# Motor.net
KiCad netlist of a schematic drawn in EAGLE
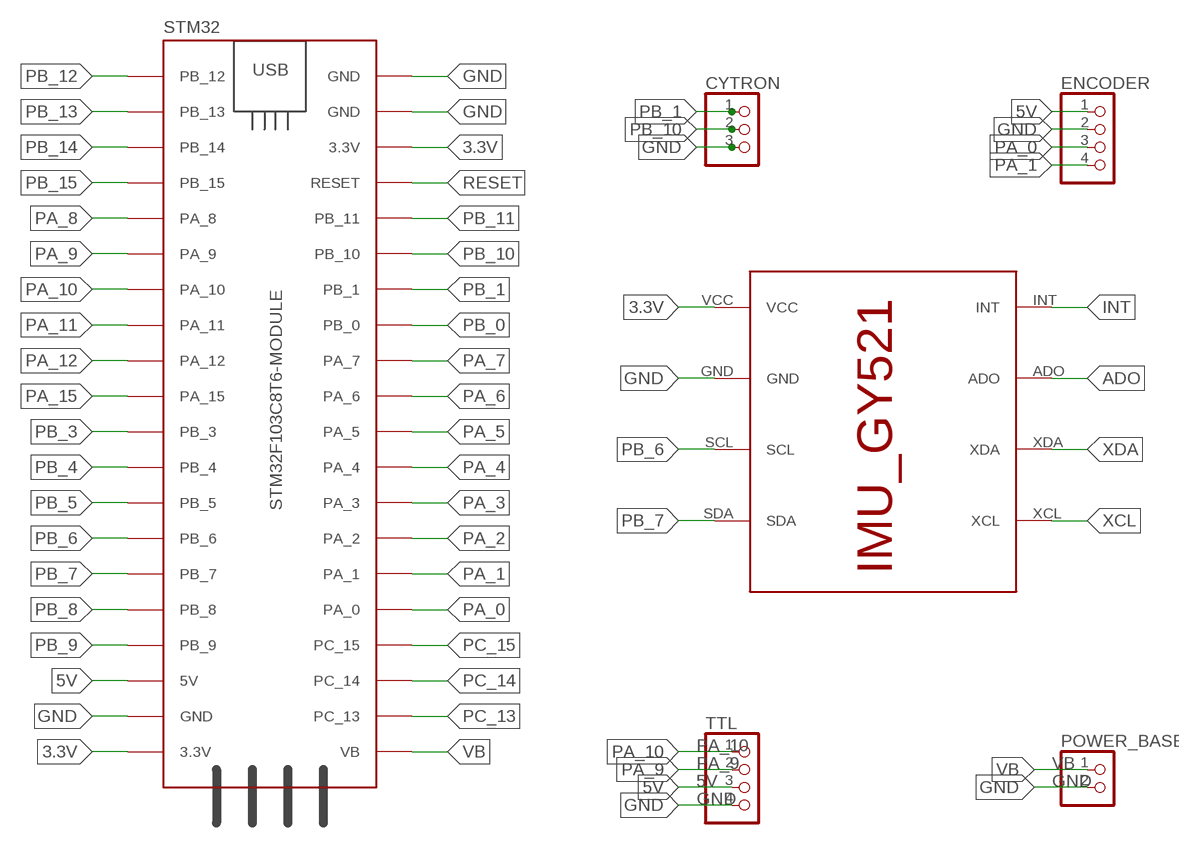
[diagram p0: schematic, sheet 1]

(export (version "E")
  (design (tool "Eeschema 10.0.6"))
  (components
    (comp (ref "CYTRON")
      (value "PINHD-3_DATA")
      (footprint "eagle-import:1X03_DATA")
      (libsource (lib "eagle-import") (part "PINHD-3_DATA"))
    )
    (comp (ref "ENCODER")
      (value "PINHD-4_DATA")
      (footprint "eagle-import:1X04_DATA")
      (libsource (lib "eagle-import") (part "PINHD-4_DATA"))
    )
    (comp (ref "IMU")
      (value "IMU_ROBOCON_GY521")
      (footprint "eagle-import:IMU_GY521")
      (libsource (lib "eagle-import") (part "IMU_ROBOCON_GY521"))
    )
    (comp (ref "POWER_BASE")
      (value "PINHD-2_DATA")
      (footprint "eagle-import:1X02_DATA")
      (libsource (lib "eagle-import") (part "PINHD-2_DATA"))
    )
    (comp (ref "STM32")
      (value "STM32F103C8T6-MODULE")
      (footprint "eagle-import:STM32F103C8T6-MODULE")
      (libsource (lib "eagle-import") (part "STM32F103C8T6-MODULE"))
    )
    (comp (ref "TTL")
      (value "PINHD-4_DATA")
      (footprint "eagle-import:1X04_DATA")
      (libsource (lib "eagle-import") (part "PINHD-4_DATA"))
    )
  )
  (nets
    (net (code "1") (name "3.3V") (class "Default")
      (node (ref "IMU") (pin "VCC") (pinfunction "VCC_VCC") (pintype "bidirectional"))
      (node (ref "STM32") (pin "3.3V_1") (pinfunction "3.3V_3.3V_1") (pintype "bidirectional"))
      (node (ref "STM32") (pin "3.3V_2") (pinfunction "3.3V_3.3V_2") (pintype "bidirectional"))
    )
    (net (code "2") (name "5V") (class "Default")
      (node (ref "ENCODER") (pin "1") (pinfunction "1_1") (pintype "passive"))
      (node (ref "STM32") (pin "5V") (pinfunction "5V_5V") (pintype "bidirectional"))
      (node (ref "TTL") (pin "3") (pinfunction "3_3") (pintype "passive"))
    )
    (net (code "3") (name "ADO") (class "Default")
      (node (ref "IMU") (pin "ADO") (pinfunction "ADO_ADO") (pintype "bidirectional"))
    )
    (net (code "4") (name "GND") (class "Default")
      (node (ref "CYTRON") (pin "3") (pinfunction "3_3") (pintype "passive"))
      (node (ref "ENCODER") (pin "2") (pinfunction "2_2") (pintype "passive"))
      (node (ref "IMU") (pin "GND") (pinfunction "GND_GND") (pintype "bidirectional"))
      (node (ref "POWER_BASE") (pin "2") (pinfunction "2_2") (pintype "passive"))
      (node (ref "STM32") (pin "GND_1") (pinfunction "GND_GND_1") (pintype "bidirectional"))
      (node (ref "STM32") (pin "GND_2") (pinfunction "GND_GND_2") (pintype "bidirectional"))
      (node (ref "STM32") (pin "GND_3") (pinfunction "GND_GND_3") (pintype "power_in"))
      (node (ref "TTL") (pin "4") (pinfunction "4_4") (pintype "passive"))
    )
    (net (code "5") (name "INT") (class "Default")
      (node (ref "IMU") (pin "INT") (pinfunction "INT_INT") (pintype "bidirectional"))
    )
    (net (code "6") (name "PA_0") (class "Default")
      (node (ref "ENCODER") (pin "3") (pinfunction "3_3") (pintype "passive"))
      (node (ref "STM32") (pin "PA_0") (pinfunction "PA_0_PA_0") (pintype "bidirectional"))
    )
    (net (code "7") (name "PA_1") (class "Default")
      (node (ref "ENCODER") (pin "4") (pinfunction "4_4") (pintype "passive"))
      (node (ref "STM32") (pin "PA_1") (pinfunction "PA_1_PA_1") (pintype "bidirectional"))
    )
    (net (code "8") (name "PA_2") (class "Default")
      (node (ref "STM32") (pin "PA_2") (pinfunction "PA_2_PA_2") (pintype "bidirectional"))
    )
    (net (code "9") (name "PA_3") (class "Default")
      (node (ref "STM32") (pin "PA_3") (pinfunction "PA_3_PA_3") (pintype "bidirectional"))
    )
    (net (code "10") (name "PA_4") (class "Default")
      (node (ref "STM32") (pin "PA_4") (pinfunction "PA_4_PA_4") (pintype "bidirectional"))
    )
    (net (code "11") (name "PA_5") (class "Default")
      (node (ref "STM32") (pin "PA_5") (pinfunction "PA_5_PA_5") (pintype "bidirectional"))
    )
    (net (code "12") (name "PA_6") (class "Default")
      (node (ref "STM32") (pin "PA_6") (pinfunction "PA_6_PA_6") (pintype "bidirectional"))
    )
    (net (code "13") (name "PA_7") (class "Default")
      (node (ref "STM32") (pin "PA_7") (pinfunction "PA_7_PA_7") (pintype "bidirectional"))
    )
    (net (code "14") (name "PA_8") (class "Default")
      (node (ref "STM32") (pin "PA_8") (pinfunction "PA_8_PA_8") (pintype "bidirectional"))
    )
    (net (code "15") (name "PA_9") (class "Default")
      (node (ref "STM32") (pin "PA_9") (pinfunction "PA_9_PA_9") (pintype "bidirectional"))
      (node (ref "TTL") (pin "2") (pinfunction "2_2") (pintype "passive"))
    )
    (net (code "16") (name "PA_10") (class "Default")
      (node (ref "STM32") (pin "PA_10") (pinfunction "PA_10_PA_10") (pintype "bidirectional"))
      (node (ref "TTL") (pin "1") (pinfunction "1_1") (pintype "passive"))
    )
    (net (code "17") (name "PA_11") (class "Default")
      (node (ref "STM32") (pin "PA_11") (pinfunction "PA_11_PA_11") (pintype "bidirectional"))
    )
    (net (code "18") (name "PA_12") (class "Default")
      (node (ref "STM32") (pin "PA_12") (pinfunction "PA_12_PA_12") (pintype "bidirectional"))
    )
    (net (code "19") (name "PA_15") (class "Default")
      (node (ref "STM32") (pin "PA_15") (pinfunction "PA_15_PA_15") (pintype "bidirectional"))
    )
    (net (code "20") (name "PB_0") (class "Default")
      (node (ref "STM32") (pin "PB_0") (pinfunction "PB_0_PB_0") (pintype "bidirectional"))
    )
    (net (code "21") (name "PB_1") (class "Default")
      (node (ref "CYTRON") (pin "1") (pinfunction "1_1") (pintype "passive"))
      (node (ref "STM32") (pin "PB_1") (pinfunction "PB_1_PB_1") (pintype "bidirectional"))
    )
    (net (code "22") (name "PB_3") (class "Default")
      (node (ref "STM32") (pin "PB_3") (pinfunction "PB_3_PB_3") (pintype "bidirectional"))
    )
    (net (code "23") (name "PB_4") (class "Default")
      (node (ref "STM32") (pin "PB_4") (pinfunction "PB_4_PB_4") (pintype "bidirectional"))
    )
    (net (code "24") (name "PB_5") (class "Default")
      (node (ref "STM32") (pin "PB_5") (pinfunction "PB_5_PB_5") (pintype "bidirectional"))
    )
    (net (code "25") (name "PB_6") (class "Default")
      (node (ref "IMU") (pin "SCL") (pinfunction "SCL_SCL") (pintype "bidirectional"))
      (node (ref "STM32") (pin "PB_6") (pinfunction "PB_6_PB_6") (pintype "bidirectional"))
    )
    (net (code "26") (name "PB_7") (class "Default")
      (node (ref "IMU") (pin "SDA") (pinfunction "SDA_SDA") (pintype "bidirectional"))
      (node (ref "STM32") (pin "PB_7") (pinfunction "PB_7_PB_7") (pintype "bidirectional"))
    )
    (net (code "27") (name "PB_8") (class "Default")
      (node (ref "STM32") (pin "PB_8") (pinfunction "PB_8_PB_8") (pintype "bidirectional"))
    )
    (net (code "28") (name "PB_9") (class "Default")
      (node (ref "STM32") (pin "PB_9") (pinfunction "PB_9_PB_9") (pintype "bidirectional"))
    )
    (net (code "29") (name "PB_10") (class "Default")
      (node (ref "CYTRON") (pin "2") (pinfunction "2_2") (pintype "passive"))
      (node (ref "STM32") (pin "PB_10") (pinfunction "PB_10_PB_10") (pintype "bidirectional"))
    )
    (net (code "30") (name "PB_11") (class "Default")
      (node (ref "STM32") (pin "PB_11") (pinfunction "PB_11_PB_11") (pintype "bidirectional"))
    )
    (net (code "31") (name "PB_12") (class "Default")
      (node (ref "STM32") (pin "PB_12") (pinfunction "PB_12_PB_12") (pintype "bidirectional"))
    )
    (net (code "32") (name "PB_13") (class "Default")
      (node (ref "STM32") (pin "PB_13") (pinfunction "PB_13_PB_13") (pintype "bidirectional"))
    )
    (net (code "33") (name "PB_14") (class "Default")
      (node (ref "STM32") (pin "PB_14") (pinfunction "PB_14_PB_14") (pintype "bidirectional"))
    )
    (net (code "34") (name "PB_15") (class "Default")
      (node (ref "STM32") (pin "PB_15") (pinfunction "PB_15_PB_15") (pintype "bidirectional"))
    )
    (net (code "35") (name "PC_13") (class "Default")
      (node (ref "STM32") (pin "PC_13") (pinfunction "PC_13_PC_13") (pintype "bidirectional"))
    )
    (net (code "36") (name "PC_14") (class "Default")
      (node (ref "STM32") (pin "PC_14") (pinfunction "PC_14_PC_14") (pintype "bidirectional"))
    )
    (net (code "37") (name "PC_15") (class "Default")
      (node (ref "STM32") (pin "PC_15") (pinfunction "PC_15_PC_15") (pintype "bidirectional"))
    )
    (net (code "38") (name "RESET") (class "Default")
      (node (ref "STM32") (pin "RESET") (pinfunction "RESET_RESET") (pintype "bidirectional"))
    )
    (net (code "39") (name "VB") (class "Default")
      (node (ref "POWER_BASE") (pin "1") (pinfunction "1_1") (pintype "passive"))
      (node (ref "STM32") (pin "VB") (pinfunction "VB_VB") (pintype "bidirectional"))
    )
    (net (code "40") (name "XCL") (class "Default")
      (node (ref "IMU") (pin "XCL") (pinfunction "XCL_XCL") (pintype "bidirectional"))
    )
    (net (code "41") (name "XDA") (class "Default")
      (node (ref "IMU") (pin "XDA") (pinfunction "XDA_XDA") (pintype "bidirectional"))
    )
  )
)
